# P05_Ethernet.net
KiCad netlist of a schematic drawn in Altium Designer
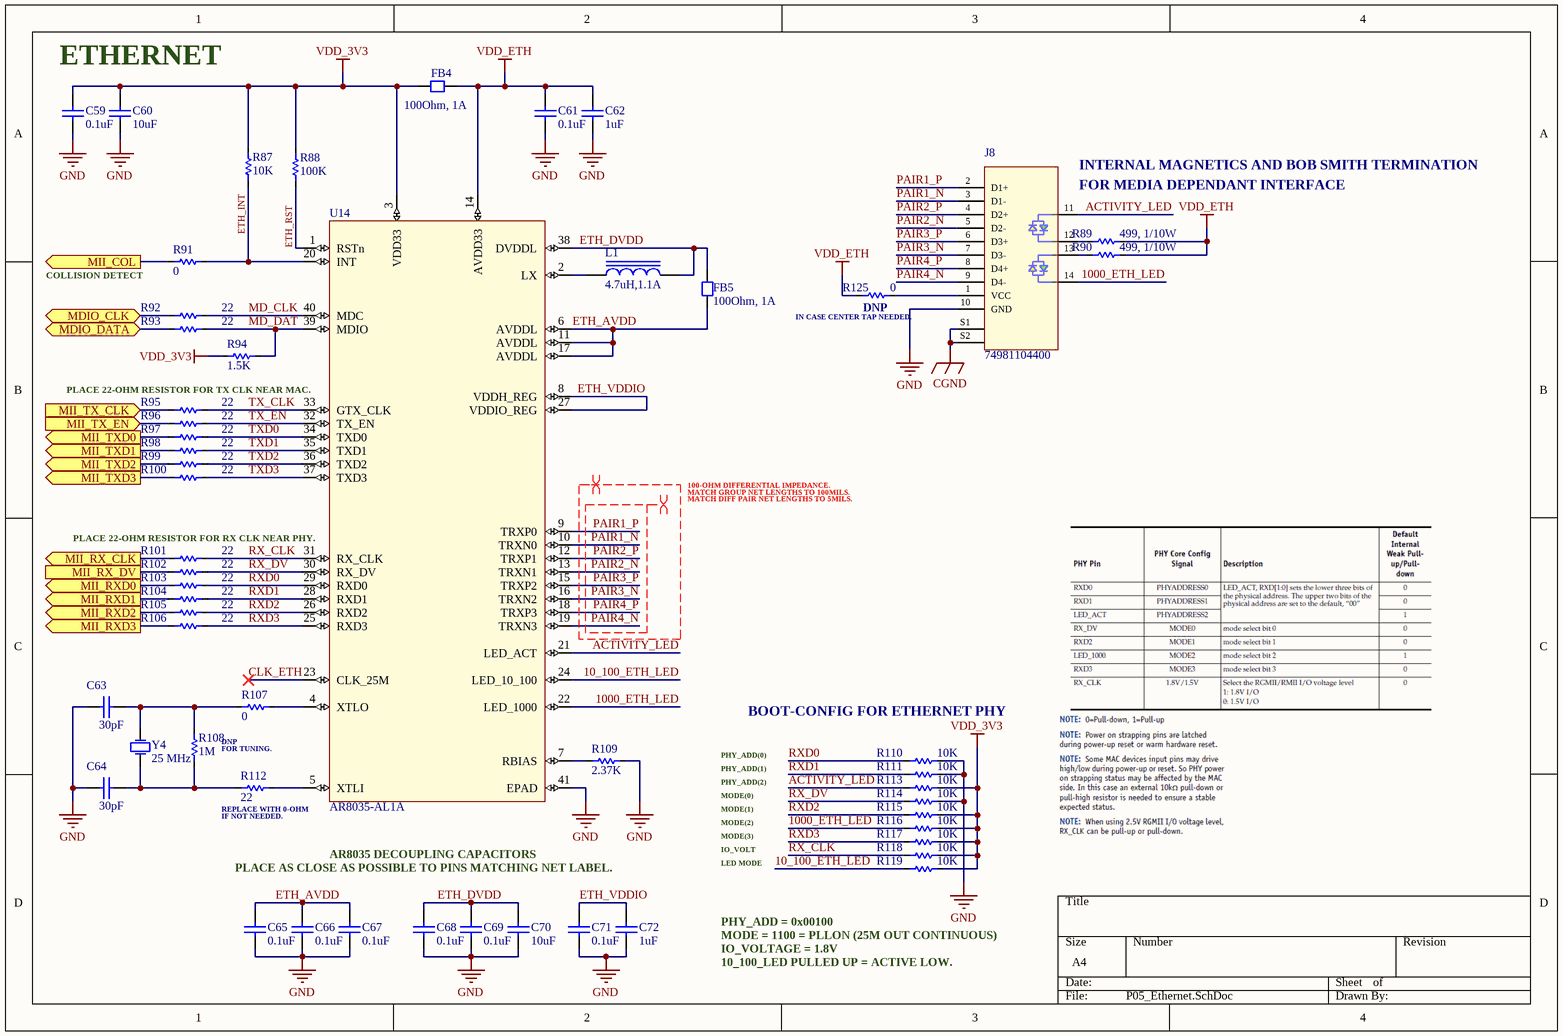
[diagram p0: P05_Ethernet.SchDoc]

(export (version "E")
  (design (tool "Eeschema 10.0.6"))
  (components
    (comp (ref "C59")
      (value "0.1uF")
      (footprint "CAP_0603")
      (description "CAP CER 0.1UF 16V X7R 0603")
      (fields (field (name "MANUFACTURER") "KEMET") (field (name "MANUFACTURER PART NO.") "C0603C104M4RACTU"))
      (libsource (lib "OSD335-X_Devboard") (part "C0603C104M4RACTU"))
    )
    (comp (ref "C60")
      (value "10uF")
      (footprint "CAP_0603")
      (description "CAP CER 10UF 10V X5R 0603")
      (fields
        (field (name "MANUFACTURER") "KEMET")
        (field (name "MANUFACTURER PART NO.") "C0603C106M8PAC7867")
      )
      (libsource (lib "OSD335-X_Devboard") (part "C0603C106M8PAC7867"))
    )
    (comp (ref "C61")
      (value "0.1uF")
      (footprint "CAP_0603")
      (description "CAP CER 0.1UF 16V X7R 0603")
      (fields (field (name "MANUFACTURER") "KEMET") (field (name "MANUFACTURER PART NO.") "C0603C104M4RACTU"))
      (libsource (lib "OSD335-X_Devboard") (part "C0603C104M4RACTU"))
    )
    (comp (ref "C62")
      (value "1uF")
      (footprint "CAP_0603")
      (description "CAP CER 1UF 16V X7R 0603")
      (fields (field (name "MANUFACTURER") "KEMET") (field (name "MANUFACTURER PART NO.") "C0603C105M4RACTU"))
      (libsource (lib "OSD335-X_Devboard") (part "C0603C105M4RACTU"))
    )
    (comp (ref "C63")
      (value "30pF")
      (footprint "CAP_0603")
      (description "CAP CER 30PF 50V C0G/NP0 0603")
      (fields
        (field (name "MANUFACTURER PART NO.") "06035A300JAT2A")
        (field (name "MANUFACTURER") "AVX Corporation")
      )
      (libsource (lib "OSD335-X_Devboard") (part "06035A300JAT2A"))
    )
    (comp (ref "C64")
      (value "30pF")
      (footprint "CAP_0603")
      (description "CAP CER 30PF 50V C0G/NP0 0603")
      (fields
        (field (name "MANUFACTURER PART NO.") "06035A300JAT2A")
        (field (name "MANUFACTURER") "AVX Corporation")
      )
      (libsource (lib "OSD335-X_Devboard") (part "06035A300JAT2A"))
    )
    (comp (ref "C65")
      (value "0.1uF")
      (footprint "CAP_0603")
      (description "CAP CER 0.1UF 16V X7R 0603")
      (fields (field (name "MANUFACTURER") "KEMET") (field (name "MANUFACTURER PART NO.") "C0603C104M4RACTU"))
      (libsource (lib "OSD335-X_Devboard") (part "C0603C104M4RACTU"))
    )
    (comp (ref "C66")
      (value "0.1uF")
      (footprint "CAP_0603")
      (description "CAP CER 0.1UF 16V X7R 0603")
      (fields (field (name "MANUFACTURER") "KEMET") (field (name "MANUFACTURER PART NO.") "C0603C104M4RACTU"))
      (libsource (lib "OSD335-X_Devboard") (part "C0603C104M4RACTU"))
    )
    (comp (ref "C67")
      (value "0.1uF")
      (footprint "CAP_0603")
      (description "CAP CER 0.1UF 16V X7R 0603")
      (fields (field (name "MANUFACTURER") "KEMET") (field (name "MANUFACTURER PART NO.") "C0603C104M4RACTU"))
      (libsource (lib "OSD335-X_Devboard") (part "C0603C104M4RACTU"))
    )
    (comp (ref "C68")
      (value "0.1uF")
      (footprint "CAP_0603")
      (description "CAP CER 0.1UF 16V X7R 0603")
      (fields (field (name "MANUFACTURER") "KEMET") (field (name "MANUFACTURER PART NO.") "C0603C104M4RACTU"))
      (libsource (lib "OSD335-X_Devboard") (part "C0603C104M4RACTU"))
    )
    (comp (ref "C69")
      (value "0.1uF")
      (footprint "CAP_0603")
      (description "CAP CER 0.1UF 16V X7R 0603")
      (fields (field (name "MANUFACTURER") "KEMET") (field (name "MANUFACTURER PART NO.") "C0603C104M4RACTU"))
      (libsource (lib "OSD335-X_Devboard") (part "C0603C104M4RACTU"))
    )
    (comp (ref "C70")
      (value "10uF")
      (footprint "CAP_0603")
      (description "CAP CER 10UF 10V X5R 0603")
      (fields
        (field (name "MANUFACTURER") "KEMET")
        (field (name "MANUFACTURER PART NO.") "C0603C106M8PAC7867")
      )
      (libsource (lib "OSD335-X_Devboard") (part "C0603C106M8PAC7867"))
    )
    (comp (ref "C71")
      (value "0.1uF")
      (footprint "CAP_0603")
      (description "CAP CER 0.1UF 16V X7R 0603")
      (fields (field (name "MANUFACTURER") "KEMET") (field (name "MANUFACTURER PART NO.") "C0603C104M4RACTU"))
      (libsource (lib "OSD335-X_Devboard") (part "C0603C104M4RACTU"))
    )
    (comp (ref "C72")
      (value "1uF")
      (footprint "CAP_0603")
      (description "CAP CER 1UF 16V X7R 0603")
      (fields (field (name "MANUFACTURER") "KEMET") (field (name "MANUFACTURER PART NO.") "C0603C105M4RACTU"))
      (libsource (lib "OSD335-X_Devboard") (part "C0603C105M4RACTU"))
    )
    (comp (ref "FB4")
      (value "100Ohm, 1A")
      (footprint "CAP_0603")
      (description "FERRITE BEAD 100 OHM 0603 1LN")
      (fields
        (field (name "MANUFACTURER PART NO.") "MPZ1608D101BTA00")
        (field (name "MANUFACTURER") "TDK Corporation")
      )
      (libsource (lib "") (part "MPZ1608D101BTA00_1"))
    )
    (comp (ref "FB5")
      (value "100Ohm, 1A")
      (footprint "CAP_0603")
      (description "FERRITE BEAD 100 OHM 0603 1LN")
      (fields
        (field (name "MANUFACTURER PART NO.") "MPZ1608D101BTA00")
        (field (name "MANUFACTURER") "TDK Corporation")
      )
      (libsource (lib "OSD335-X_Devboard") (part "MPZ1608D101BTA00"))
    )
    (comp (ref "J8")
      (value "74981104400")
      (footprint "74981104400")
      (description "WE-RJ45LAN INTEGRATED RJ45 TRANS")
      (fields (field (name "MANUFACTURER") "Wurth Elektronik"))
      (libsource (lib "OSD335-X_Devboard") (part "74981104400"))
    )
    (comp (ref "L1")
      (value "4.7uH,1.1A")
      (footprint "IND_1008")
      (description "FIXED IND 4.7UH 1.1A 110MOHM SMD")
      (fields
        (field (name "MANUFACTURER") "Bourns Inc.")
        (field (name "MANUFACTURER PART NO.") "CVH252009-4R7M")
      )
      (libsource (lib "OSD335-X_Devboard") (part "CVH252009-4R7M"))
    )
    (comp (ref "R87")
      (value "10K")
      (footprint "RES_0603")
      (description "RES SMD 10K OHM 1% 1/10W 0603")
      (fields (field (name "TOLERANCE") "1%") (field (name "MANUFACTURER") "Yageo"))
      (libsource (lib "OSD335-X_Devboard") (part "RC0603FR-0710KL"))
    )
    (comp (ref "R88")
      (value "100K")
      (footprint "RES_0603")
      (description "RES SMD 100K OHM 1% 1/10W 0603")
      (fields (field (name "TOLERANCE") "1%") (field (name "MANUFACTURER") "Yageo"))
      (libsource (lib "OSD335-X_Devboard") (part "RC0603FR-07100KL"))
    )
    (comp (ref "R89")
      (value "499, 1/10W")
      (footprint "RES_0603")
      (description "RES SMD 499 OHM 1% 1/10W 0603")
      (fields (field (name "TOLERANCE") "1%") (field (name "MANUFACTURER") "Yageo"))
      (libsource (lib "OSD335-X_Devboard") (part "RC0603FR-07499RL"))
    )
    (comp (ref "R90")
      (value "499, 1/10W")
      (footprint "RES_0603")
      (description "RES SMD 499 OHM 1% 1/10W 0603")
      (fields (field (name "TOLERANCE") "1%") (field (name "MANUFACTURER") "Yageo"))
      (libsource (lib "OSD335-X_Devboard") (part "RC0603FR-07499RL"))
    )
    (comp (ref "R91")
      (value "0")
      (footprint "RES_0603")
      (description "RES SMD 0 OHM JUMPER 1/10W 0603")
      (fields (field (name "MANUFACTURER") "Yageo") (field (name "MANUFACTURER PART NO.") "RC0603JR-070RL"))
      (libsource (lib "OSD335-X_Devboard") (part "RC0603JR-070RL"))
    )
    (comp (ref "R92")
      (value "22")
      (footprint "RES_0603")
      (description "RES SMD 22 OHM 5% 1/10W 0603")
      (fields (field (name "TOLERANCE") "5%") (field (name "MANUFACTURER") "Yageo"))
      (libsource (lib "OSD335-X_Devboard") (part "RC0603JR-0722RL"))
    )
    (comp (ref "R93")
      (value "22")
      (footprint "RES_0603")
      (description "RES SMD 22 OHM 5% 1/10W 0603")
      (fields (field (name "TOLERANCE") "5%") (field (name "MANUFACTURER") "Yageo"))
      (libsource (lib "OSD335-X_Devboard") (part "RC0603JR-0722RL"))
    )
    (comp (ref "R94")
      (value "1.5K")
      (footprint "RES_0603")
      (description "RES SMD 1.5K OHM 1% 1/10W 0603")
      (fields (field (name "TOLERANCE") "1%") (field (name "MANUFACTURER") "Yageo"))
      (libsource (lib "OSD335-X_Devboard") (part "RC0603FR-071K5L"))
    )
    (comp (ref "R95")
      (value "22")
      (footprint "RES_0603")
      (description "RES SMD 22 OHM 5% 1/10W 0603")
      (fields (field (name "TOLERANCE") "5%") (field (name "MANUFACTURER") "Yageo"))
      (libsource (lib "OSD335-X_Devboard") (part "RC0603JR-0722RL"))
    )
    (comp (ref "R96")
      (value "22")
      (footprint "RES_0603")
      (description "RES SMD 22 OHM 5% 1/10W 0603")
      (fields (field (name "TOLERANCE") "5%") (field (name "MANUFACTURER") "Yageo"))
      (libsource (lib "OSD335-X_Devboard") (part "RC0603JR-0722RL"))
    )
    (comp (ref "R97")
      (value "22")
      (footprint "RES_0603")
      (description "RES SMD 22 OHM 5% 1/10W 0603")
      (fields (field (name "TOLERANCE") "5%") (field (name "MANUFACTURER") "Yageo"))
      (libsource (lib "OSD335-X_Devboard") (part "RC0603JR-0722RL"))
    )
    (comp (ref "R98")
      (value "22")
      (footprint "RES_0603")
      (description "RES SMD 22 OHM 5% 1/10W 0603")
      (fields (field (name "TOLERANCE") "5%") (field (name "MANUFACTURER") "Yageo"))
      (libsource (lib "OSD335-X_Devboard") (part "RC0603JR-0722RL"))
    )
    (comp (ref "R99")
      (value "22")
      (footprint "RES_0603")
      (description "RES SMD 22 OHM 5% 1/10W 0603")
      (fields (field (name "TOLERANCE") "5%") (field (name "MANUFACTURER") "Yageo"))
      (libsource (lib "OSD335-X_Devboard") (part "RC0603JR-0722RL"))
    )
    (comp (ref "R100")
      (value "22")
      (footprint "RES_0603")
      (description "RES SMD 22 OHM 5% 1/10W 0603")
      (fields (field (name "TOLERANCE") "5%") (field (name "MANUFACTURER") "Yageo"))
      (libsource (lib "OSD335-X_Devboard") (part "RC0603JR-0722RL"))
    )
    (comp (ref "R101")
      (value "22")
      (footprint "RES_0603")
      (description "RES SMD 22 OHM 5% 1/10W 0603")
      (fields (field (name "TOLERANCE") "5%") (field (name "MANUFACTURER") "Yageo"))
      (libsource (lib "OSD335-X_Devboard") (part "RC0603JR-0722RL"))
    )
    (comp (ref "R102")
      (value "22")
      (footprint "RES_0603")
      (description "RES SMD 22 OHM 5% 1/10W 0603")
      (fields (field (name "TOLERANCE") "5%") (field (name "MANUFACTURER") "Yageo"))
      (libsource (lib "OSD335-X_Devboard") (part "RC0603JR-0722RL"))
    )
    (comp (ref "R103")
      (value "22")
      (footprint "RES_0603")
      (description "RES SMD 22 OHM 5% 1/10W 0603")
      (fields (field (name "TOLERANCE") "5%") (field (name "MANUFACTURER") "Yageo"))
      (libsource (lib "OSD335-X_Devboard") (part "RC0603JR-0722RL"))
    )
    (comp (ref "R104")
      (value "22")
      (footprint "RES_0603")
      (description "RES SMD 22 OHM 5% 1/10W 0603")
      (fields (field (name "TOLERANCE") "5%") (field (name "MANUFACTURER") "Yageo"))
      (libsource (lib "OSD335-X_Devboard") (part "RC0603JR-0722RL"))
    )
    (comp (ref "R105")
      (value "22")
      (footprint "RES_0603")
      (description "RES SMD 22 OHM 5% 1/10W 0603")
      (fields (field (name "TOLERANCE") "5%") (field (name "MANUFACTURER") "Yageo"))
      (libsource (lib "OSD335-X_Devboard") (part "RC0603JR-0722RL"))
    )
    (comp (ref "R106")
      (value "22")
      (footprint "RES_0603")
      (description "RES SMD 22 OHM 5% 1/10W 0603")
      (fields (field (name "TOLERANCE") "5%") (field (name "MANUFACTURER") "Yageo"))
      (libsource (lib "OSD335-X_Devboard") (part "RC0603JR-0722RL"))
    )
    (comp (ref "R107")
      (value "0")
      (footprint "RES_0603")
      (description "RES SMD 0 OHM JUMPER 1/10W 0603")
      (fields (field (name "MANUFACTURER") "Yageo") (field (name "MANUFACTURER PART NO.") "RC0603JR-070RL"))
      (libsource (lib "OSD335-X_Devboard") (part "RC0603JR-070RL"))
    )
    (comp (ref "R108")
      (value "1M")
      (footprint "RES_0603")
      (description "RES SMD 1M OHM 5% 1/10W 0603")
      (fields (field (name "TOLERANCE") "5%") (field (name "MANUFACTURER") "Yageo"))
      (libsource (lib "OSD335-X_Devboard") (part "RC0603JR-071ML"))
    )
    (comp (ref "R109")
      (value "2.37K")
      (footprint "RES_0603")
      (description "RES SMD 2.37K OHM 1% 1/10W 0603")
      (fields (field (name "TOLERANCE") "1%") (field (name "MANUFACTURER") "Yageo"))
      (libsource (lib "OSD335-X_Devboard") (part "RC0603FR-072K37L"))
    )
    (comp (ref "R110")
      (value "10K")
      (footprint "RES_0603")
      (description "RES SMD 10K OHM 1% 1/10W 0603")
      (fields (field (name "TOLERANCE") "1%") (field (name "MANUFACTURER") "Yageo"))
      (libsource (lib "OSD335-X_Devboard") (part "RC0603FR-0710KL"))
    )
    (comp (ref "R111")
      (value "10K")
      (footprint "RES_0603")
      (description "RES SMD 10K OHM 1% 1/10W 0603")
      (fields (field (name "TOLERANCE") "1%") (field (name "MANUFACTURER") "Yageo"))
      (libsource (lib "OSD335-X_Devboard") (part "RC0603FR-0710KL"))
    )
    (comp (ref "R112")
      (value "22")
      (footprint "RES_0603")
      (description "RES SMD 22 OHM 5% 1/10W 0603")
      (fields (field (name "TOLERANCE") "5%") (field (name "MANUFACTURER") "Yageo"))
      (libsource (lib "OSD335-X_Devboard") (part "RC0603JR-0722RL"))
    )
    (comp (ref "R113")
      (value "10K")
      (footprint "RES_0603")
      (description "RES SMD 10K OHM 1% 1/10W 0603")
      (fields (field (name "TOLERANCE") "1%") (field (name "MANUFACTURER") "Yageo"))
      (libsource (lib "OSD335-X_Devboard") (part "RC0603FR-0710KL"))
    )
    (comp (ref "R114")
      (value "10K")
      (footprint "RES_0603")
      (description "RES SMD 10K OHM 1% 1/10W 0603")
      (fields (field (name "TOLERANCE") "1%") (field (name "MANUFACTURER") "Yageo"))
      (libsource (lib "OSD335-X_Devboard") (part "RC0603FR-0710KL"))
    )
    (comp (ref "R115")
      (value "10K")
      (footprint "RES_0603")
      (description "RES SMD 10K OHM 1% 1/10W 0603")
      (fields (field (name "TOLERANCE") "1%") (field (name "MANUFACTURER") "Yageo"))
      (libsource (lib "OSD335-X_Devboard") (part "RC0603FR-0710KL"))
    )
    (comp (ref "R116")
      (value "10K")
      (footprint "RES_0603")
      (description "RES SMD 10K OHM 1% 1/10W 0603")
      (fields (field (name "TOLERANCE") "1%") (field (name "MANUFACTURER") "Yageo"))
      (libsource (lib "OSD335-X_Devboard") (part "RC0603FR-0710KL"))
    )
    (comp (ref "R117")
      (value "10K")
      (footprint "RES_0603")
      (description "RES SMD 10K OHM 1% 1/10W 0603")
      (fields (field (name "TOLERANCE") "1%") (field (name "MANUFACTURER") "Yageo"))
      (libsource (lib "OSD335-X_Devboard") (part "RC0603FR-0710KL"))
    )
    (comp (ref "R118")
      (value "10K")
      (footprint "RES_0603")
      (description "RES SMD 10K OHM 1% 1/10W 0603")
      (fields (field (name "TOLERANCE") "1%") (field (name "MANUFACTURER") "Yageo"))
      (libsource (lib "OSD335-X_Devboard") (part "RC0603FR-0710KL"))
    )
    (comp (ref "R119")
      (value "10K")
      (footprint "RES_0603")
      (description "RES SMD 10K OHM 1% 1/10W 0603")
      (fields (field (name "TOLERANCE") "1%") (field (name "MANUFACTURER") "Yageo"))
      (libsource (lib "OSD335-X_Devboard") (part "RC0603FR-0710KL"))
    )
    (comp (ref "R125")
      (value "0")
      (footprint "RES_0603")
      (description "RES SMD 0 OHM JUMPER 1/10W 0603")
      (fields (field (name "MANUFACTURER") "Yageo") (field (name "MANUFACTURER PART NO.") "RC0603JR-070RL"))
      (libsource (lib "OSD335-X_Devboard") (part "RC0603JR-070RL"))
    )
    (comp (ref "U14")
      (value "AR8035-AL1A")
      (footprint "QFN-40_5X5MM")
      (description "IC ETHERNET TRANSCEIVER FULL 1/1 GIGABIT 40QFN")
      (fields (field (name "MANUFACTURER") "Qualcomm"))
      (libsource (lib "OSD335-X_Devboard") (part "AR8035-AL1A"))
    )
    (comp (ref "Y4")
      (value "25 MHz")
      (footprint "7A-24MHz")
      (description "CRYSTAL 25.0000MHZ 18PF SMD")
      (fields
        (field (name "MANUFACTURER") "TXC CORPORATION")
        (field (name "MANUFACTURER PART NO.") "7A-25.000MAAJ-T")
      )
      (libsource (lib "OSD335-X_Devboard") (part "7A-25.000MAAJ-T"))
    )
  )
  (nets
    (net (code "1") (name "/10_100_ETH_LED") (class "Default")
      (node (ref "R119") (pin "1") (pinfunction "1_1") (pintype "passive"))
      (node (ref "U14") (pin "24") (pinfunction "LED_10_100_24") (pintype "bidirectional"))
    )
    (net (code "2") (name "/1000_ETH_LED") (class "Default")
      (node (ref "J8") (pin "14") (pinfunction "14_14") (pintype "passive"))
      (node (ref "R116") (pin "1") (pinfunction "1_1") (pintype "passive"))
      (node (ref "U14") (pin "22") (pinfunction "LED_1000_22") (pintype "bidirectional"))
    )
    (net (code "3") (name "/ACTIVITY_LED") (class "Default")
      (node (ref "J8") (pin "11") (pinfunction "11_11") (pintype "passive"))
      (node (ref "R113") (pin "1") (pinfunction "1_1") (pintype "passive"))
      (node (ref "U14") (pin "21") (pinfunction "LED_ACT_21") (pintype "bidirectional"))
    )
    (net (code "4") (name "/CLK_ETH") (class "Default")
      (node (ref "U14") (pin "23") (pinfunction "CLK_25M_23") (pintype "bidirectional+no_connect"))
    )
    (net (code "5") (name "/ETH_AVDD") (class "Default")
      (node (ref "C65") (pin "2") (pinfunction "2_2") (pintype "passive"))
      (node (ref "C66") (pin "2") (pinfunction "2_2") (pintype "passive"))
      (node (ref "C67") (pin "2") (pinfunction "2_2") (pintype "passive"))
      (node (ref "FB5") (pin "1") (pinfunction "1_1") (pintype "passive"))
      (node (ref "U14") (pin "11") (pinfunction "AVDDL_11") (pintype "bidirectional"))
      (node (ref "U14") (pin "17") (pinfunction "AVDDL_17") (pintype "bidirectional"))
      (node (ref "U14") (pin "6") (pinfunction "AVDDL_6") (pintype "bidirectional"))
    )
    (net (code "6") (name "/ETH_DVDD") (class "Default")
      (node (ref "C68") (pin "2") (pinfunction "2_2") (pintype "passive"))
      (node (ref "C69") (pin "2") (pinfunction "2_2") (pintype "passive"))
      (node (ref "C70") (pin "2") (pinfunction "2_2") (pintype "passive"))
      (node (ref "FB5") (pin "2") (pinfunction "2_2") (pintype "passive"))
      (node (ref "L1") (pin "2") (pinfunction "2_2") (pintype "passive"))
      (node (ref "U14") (pin "38") (pinfunction "DVDDL_38") (pintype "bidirectional"))
    )
    (net (code "7") (name "/ETH_INT") (class "Default")
      (node (ref "R87") (pin "1") (pinfunction "1_1") (pintype "passive"))
      (node (ref "R91") (pin "2") (pinfunction "2_2") (pintype "passive"))
      (node (ref "U14") (pin "20") (pinfunction "INT_20") (pintype "bidirectional"))
    )
    (net (code "8") (name "/ETH_RST") (class "Default")
      (node (ref "R88") (pin "1") (pinfunction "1_1") (pintype "passive"))
      (node (ref "U14") (pin "1") (pinfunction "RSTn_1") (pintype "bidirectional"))
    )
    (net (code "9") (name "/ETH_VDDIO") (class "Default")
      (node (ref "C71") (pin "2") (pinfunction "2_2") (pintype "passive"))
      (node (ref "C72") (pin "2") (pinfunction "2_2") (pintype "passive"))
      (node (ref "U14") (pin "27") (pinfunction "VDDIO_REG_27") (pintype "bidirectional"))
      (node (ref "U14") (pin "8") (pinfunction "VDDH_REG_8") (pintype "bidirectional"))
    )
    (net (code "10") (name "/MDIO_CLK") (class "Default")
      (node (ref "R92") (pin "1") (pinfunction "1_1") (pintype "passive"))
    )
    (net (code "11") (name "/MDIO_DATA") (class "Default")
      (node (ref "R93") (pin "1") (pinfunction "1_1") (pintype "passive"))
    )
    (net (code "12") (name "/MD_CLK") (class "Default")
      (node (ref "R92") (pin "2") (pinfunction "2_2") (pintype "passive"))
      (node (ref "U14") (pin "40") (pinfunction "MDC_40") (pintype "bidirectional"))
    )
    (net (code "13") (name "/MD_DAT") (class "Default")
      (node (ref "R93") (pin "2") (pinfunction "2_2") (pintype "passive"))
      (node (ref "R94") (pin "1") (pinfunction "1_1") (pintype "passive"))
      (node (ref "U14") (pin "39") (pinfunction "MDIO_39") (pintype "bidirectional"))
    )
    (net (code "14") (name "/MII_COL") (class "Default")
      (node (ref "R91") (pin "1") (pinfunction "1_1") (pintype "passive"))
    )
    (net (code "15") (name "/MII_RXD0") (class "Default")
      (node (ref "R103") (pin "1") (pinfunction "1_1") (pintype "passive"))
    )
    (net (code "16") (name "/MII_RXD1") (class "Default")
      (node (ref "R104") (pin "1") (pinfunction "1_1") (pintype "passive"))
    )
    (net (code "17") (name "/MII_RXD2") (class "Default")
      (node (ref "R105") (pin "1") (pinfunction "1_1") (pintype "passive"))
    )
    (net (code "18") (name "/MII_RXD3") (class "Default")
      (node (ref "R106") (pin "1") (pinfunction "1_1") (pintype "passive"))
    )
    (net (code "19") (name "/MII_RX_CLK") (class "Default")
      (node (ref "R101") (pin "1") (pinfunction "1_1") (pintype "passive"))
    )
    (net (code "20") (name "/MII_RX_DV") (class "Default")
      (node (ref "R102") (pin "1") (pinfunction "1_1") (pintype "passive"))
    )
    (net (code "21") (name "/MII_TXD0") (class "Default")
      (node (ref "R97") (pin "1") (pinfunction "1_1") (pintype "passive"))
    )
    (net (code "22") (name "/MII_TXD1") (class "Default")
      (node (ref "R98") (pin "1") (pinfunction "1_1") (pintype "passive"))
    )
    (net (code "23") (name "/MII_TXD2") (class "Default")
      (node (ref "R99") (pin "1") (pinfunction "1_1") (pintype "passive"))
    )
    (net (code "24") (name "/MII_TXD3") (class "Default")
      (node (ref "R100") (pin "1") (pinfunction "1_1") (pintype "passive"))
    )
    (net (code "25") (name "/MII_TX_CLK") (class "Default")
      (node (ref "R95") (pin "1") (pinfunction "1_1") (pintype "passive"))
    )
    (net (code "26") (name "/MII_TX_EN") (class "Default")
      (node (ref "R96") (pin "1") (pinfunction "1_1") (pintype "passive"))
    )
    (net (code "27") (name "/PAIR1_N") (class "Default")
      (node (ref "J8") (pin "3") (pinfunction "D1-_3") (pintype "passive"))
      (node (ref "U14") (pin "10") (pinfunction "TRXN0_10") (pintype "bidirectional"))
    )
    (net (code "28") (name "/PAIR1_P") (class "Default")
      (node (ref "J8") (pin "2") (pinfunction "D1+_2") (pintype "passive"))
      (node (ref "U14") (pin "9") (pinfunction "TRXP0_9") (pintype "bidirectional"))
    )
    (net (code "29") (name "/PAIR2_N") (class "Default")
      (node (ref "J8") (pin "5") (pinfunction "D2-_5") (pintype "passive"))
      (node (ref "U14") (pin "13") (pinfunction "TRXN1_13") (pintype "bidirectional"))
    )
    (net (code "30") (name "/PAIR2_P") (class "Default")
      (node (ref "J8") (pin "4") (pinfunction "D2+_4") (pintype "passive"))
      (node (ref "U14") (pin "12") (pinfunction "TRXP1_12") (pintype "bidirectional"))
    )
    (net (code "31") (name "/PAIR3_N") (class "Default")
      (node (ref "J8") (pin "7") (pinfunction "D3-_7") (pintype "passive"))
      (node (ref "U14") (pin "16") (pinfunction "TRXN2_16") (pintype "bidirectional"))
    )
    (net (code "32") (name "/PAIR3_P") (class "Default")
      (node (ref "J8") (pin "6") (pinfunction "D3+_6") (pintype "passive"))
      (node (ref "U14") (pin "15") (pinfunction "TRXP2_15") (pintype "bidirectional"))
    )
    (net (code "33") (name "/PAIR4_N") (class "Default")
      (node (ref "J8") (pin "9") (pinfunction "D4-_9") (pintype "passive"))
      (node (ref "U14") (pin "19") (pinfunction "TRXN3_19") (pintype "bidirectional"))
    )
    (net (code "34") (name "/PAIR4_P") (class "Default")
      (node (ref "J8") (pin "8") (pinfunction "D4+_8") (pintype "passive"))
      (node (ref "U14") (pin "18") (pinfunction "TRXP3_18") (pintype "bidirectional"))
    )
    (net (code "35") (name "/RXD0") (class "Default")
      (node (ref "R103") (pin "2") (pinfunction "2_2") (pintype "passive"))
      (node (ref "R110") (pin "1") (pinfunction "1_1") (pintype "passive"))
      (node (ref "U14") (pin "29") (pinfunction "RXD0_29") (pintype "bidirectional"))
    )
    (net (code "36") (name "/RXD1") (class "Default")
      (node (ref "R104") (pin "2") (pinfunction "2_2") (pintype "passive"))
      (node (ref "R111") (pin "1") (pinfunction "1_1") (pintype "passive"))
      (node (ref "U14") (pin "28") (pinfunction "RXD1_28") (pintype "bidirectional"))
    )
    (net (code "37") (name "/RXD2") (class "Default")
      (node (ref "R105") (pin "2") (pinfunction "2_2") (pintype "passive"))
      (node (ref "R115") (pin "1") (pinfunction "1_1") (pintype "passive"))
      (node (ref "U14") (pin "26") (pinfunction "RXD2_26") (pintype "bidirectional"))
    )
    (net (code "38") (name "/RXD3") (class "Default")
      (node (ref "R106") (pin "2") (pinfunction "2_2") (pintype "passive"))
      (node (ref "R117") (pin "1") (pinfunction "1_1") (pintype "passive"))
      (node (ref "U14") (pin "25") (pinfunction "RXD3_25") (pintype "bidirectional"))
    )
    (net (code "39") (name "/RX_CLK") (class "Default")
      (node (ref "R101") (pin "2") (pinfunction "2_2") (pintype "passive"))
      (node (ref "R118") (pin "1") (pinfunction "1_1") (pintype "passive"))
      (node (ref "U14") (pin "31") (pinfunction "RX_CLK_31") (pintype "bidirectional"))
    )
    (net (code "40") (name "/RX_DV") (class "Default")
      (node (ref "R102") (pin "2") (pinfunction "2_2") (pintype "passive"))
      (node (ref "R114") (pin "1") (pinfunction "1_1") (pintype "passive"))
      (node (ref "U14") (pin "30") (pinfunction "RX_DV_30") (pintype "bidirectional"))
    )
    (net (code "41") (name "/TXD0") (class "Default")
      (node (ref "R97") (pin "2") (pinfunction "2_2") (pintype "passive"))
      (node (ref "U14") (pin "34") (pinfunction "TXD0_34") (pintype "bidirectional"))
    )
    (net (code "42") (name "/TXD1") (class "Default")
      (node (ref "R98") (pin "2") (pinfunction "2_2") (pintype "passive"))
      (node (ref "U14") (pin "35") (pinfunction "TXD1_35") (pintype "bidirectional"))
    )
    (net (code "43") (name "/TXD2") (class "Default")
      (node (ref "R99") (pin "2") (pinfunction "2_2") (pintype "passive"))
      (node (ref "U14") (pin "36") (pinfunction "TXD2_36") (pintype "bidirectional"))
    )
    (net (code "44") (name "/TXD3") (class "Default")
      (node (ref "R100") (pin "2") (pinfunction "2_2") (pintype "passive"))
      (node (ref "U14") (pin "37") (pinfunction "TXD3_37") (pintype "bidirectional"))
    )
    (net (code "45") (name "/TX_CLK") (class "Default")
      (node (ref "R95") (pin "2") (pinfunction "2_2") (pintype "passive"))
      (node (ref "U14") (pin "33") (pinfunction "GTX_CLK_33") (pintype "bidirectional"))
    )
    (net (code "46") (name "/TX_EN") (class "Default")
      (node (ref "R96") (pin "2") (pinfunction "2_2") (pintype "passive"))
      (node (ref "U14") (pin "32") (pinfunction "TX_EN_32") (pintype "bidirectional"))
    )
    (net (code "47") (name "CGND") (class "Default")
      (node (ref "J8") (pin "S1") (pinfunction "Shield_S1") (pintype "passive"))
      (node (ref "J8") (pin "S2") (pinfunction "Shield_S2") (pintype "passive"))
    )
    (net (code "48") (name "GND") (class "Default")
      (node (ref "C59") (pin "1") (pinfunction "1_1") (pintype "passive"))
      (node (ref "C60") (pin "1") (pinfunction "1_1") (pintype "passive"))
      (node (ref "C61") (pin "1") (pinfunction "1_1") (pintype "passive"))
      (node (ref "C62") (pin "1") (pinfunction "1_1") (pintype "passive"))
      (node (ref "C63") (pin "1") (pinfunction "N_1") (pintype "passive"))
      (node (ref "C64") (pin "1") (pinfunction "N_1") (pintype "passive"))
      (node (ref "C65") (pin "1") (pinfunction "1_1") (pintype "passive"))
      (node (ref "C66") (pin "1") (pinfunction "1_1") (pintype "passive"))
      (node (ref "C67") (pin "1") (pinfunction "1_1") (pintype "passive"))
      (node (ref "C68") (pin "1") (pinfunction "1_1") (pintype "passive"))
      (node (ref "C69") (pin "1") (pinfunction "1_1") (pintype "passive"))
      (node (ref "C70") (pin "1") (pinfunction "1_1") (pintype "passive"))
      (node (ref "C71") (pin "1") (pinfunction "1_1") (pintype "passive"))
      (node (ref "C72") (pin "1") (pinfunction "1_1") (pintype "passive"))
      (node (ref "J8") (pin "10") (pinfunction "GND_10") (pintype "passive"))
      (node (ref "R109") (pin "2") (pinfunction "2_2") (pintype "passive"))
      (node (ref "R110") (pin "2") (pinfunction "2_2") (pintype "passive"))
      (node (ref "R111") (pin "2") (pinfunction "2_2") (pintype "passive"))
      (node (ref "R114") (pin "2") (pinfunction "2_2") (pintype "passive"))
      (node (ref "U14") (pin "41") (pinfunction "EPAD_41") (pintype "bidirectional"))
    )
    (net (code "49") (name "Net-(C63-P)") (class "Default")
      (node (ref "C63") (pin "2") (pinfunction "P_2") (pintype "passive"))
      (node (ref "R107") (pin "1") (pinfunction "1_1") (pintype "passive"))
      (node (ref "R108") (pin "2") (pinfunction "2_2") (pintype "passive"))
      (node (ref "Y4") (pin "2") (pinfunction "OSC2_2") (pintype "passive"))
    )
    (net (code "50") (name "Net-(C64-P)") (class "Default")
      (node (ref "C64") (pin "2") (pinfunction "P_2") (pintype "passive"))
      (node (ref "R108") (pin "1") (pinfunction "1_1") (pintype "passive"))
      (node (ref "R112") (pin "1") (pinfunction "1_1") (pintype "passive"))
      (node (ref "Y4") (pin "1") (pinfunction "OSC1_1") (pintype "passive"))
    )
    (net (code "51") (name "Net-(J8-Pad12)") (class "Default")
      (node (ref "J8") (pin "12") (pinfunction "12_12") (pintype "passive"))
      (node (ref "R89") (pin "1") (pinfunction "1_1") (pintype "passive"))
    )
    (net (code "52") (name "Net-(J8-Pad13)") (class "Default")
      (node (ref "J8") (pin "13") (pinfunction "13_13") (pintype "passive"))
      (node (ref "R90") (pin "1") (pinfunction "1_1") (pintype "passive"))
    )
    (net (code "53") (name "Net-(J8-VCC)") (class "Default")
      (node (ref "J8") (pin "1") (pinfunction "VCC_1") (pintype "passive"))
      (node (ref "R125") (pin "2") (pinfunction "2_2") (pintype "passive"))
    )
    (net (code "54") (name "Net-(U14-LX)") (class "Default")
      (node (ref "L1") (pin "1") (pinfunction "1_1") (pintype "passive"))
      (node (ref "U14") (pin "2") (pinfunction "LX_2") (pintype "bidirectional"))
    )
    (net (code "55") (name "Net-(U14-RBIAS)") (class "Default")
      (node (ref "R109") (pin "1") (pinfunction "1_1") (pintype "passive"))
      (node (ref "U14") (pin "7") (pinfunction "RBIAS_7") (pintype "bidirectional"))
    )
    (net (code "56") (name "Net-(U14-XTLI)") (class "Default")
      (node (ref "R112") (pin "2") (pinfunction "2_2") (pintype "passive"))
      (node (ref "U14") (pin "5") (pinfunction "XTLI_5") (pintype "bidirectional"))
    )
    (net (code "57") (name "Net-(U14-XTLO)") (class "Default")
      (node (ref "R107") (pin "2") (pinfunction "2_2") (pintype "passive"))
      (node (ref "U14") (pin "4") (pinfunction "XTLO_4") (pintype "bidirectional"))
    )
    (net (code "58") (name "VDD_3V3") (class "Default")
      (node (ref "C59") (pin "2") (pinfunction "2_2") (pintype "passive"))
      (node (ref "C60") (pin "2") (pinfunction "2_2") (pintype "passive"))
      (node (ref "FB4") (pin "1") (pinfunction "1_1") (pintype "passive"))
      (node (ref "R113") (pin "2") (pinfunction "2_2") (pintype "passive"))
      (node (ref "R115") (pin "2") (pinfunction "2_2") (pintype "passive"))
      (node (ref "R116") (pin "2") (pinfunction "2_2") (pintype "passive"))
      (node (ref "R117") (pin "2") (pinfunction "2_2") (pintype "passive"))
      (node (ref "R118") (pin "2") (pinfunction "2_2") (pintype "passive"))
      (node (ref "R119") (pin "2") (pinfunction "2_2") (pintype "passive"))
      (node (ref "R87") (pin "2") (pinfunction "2_2") (pintype "passive"))
      (node (ref "R88") (pin "2") (pinfunction "2_2") (pintype "passive"))
      (node (ref "R94") (pin "2") (pinfunction "2_2") (pintype "passive"))
      (node (ref "U14") (pin "3") (pinfunction "VDD33_3") (pintype "bidirectional"))
    )
    (net (code "59") (name "VDD_ETH") (class "Default")
      (node (ref "C61") (pin "2") (pinfunction "2_2") (pintype "passive"))
      (node (ref "C62") (pin "2") (pinfunction "2_2") (pintype "passive"))
      (node (ref "FB4") (pin "2") (pinfunction "2_2") (pintype "passive"))
      (node (ref "R125") (pin "1") (pinfunction "1_1") (pintype "passive"))
      (node (ref "R89") (pin "2") (pinfunction "2_2") (pintype "passive"))
      (node (ref "R90") (pin "2") (pinfunction "2_2") (pintype "passive"))
      (node (ref "U14") (pin "14") (pinfunction "AVDD33_14") (pintype "bidirectional"))
    )
  )
)
